# Percep_o_Externa.net
KiCad netlist of a schematic drawn in Altium Designer
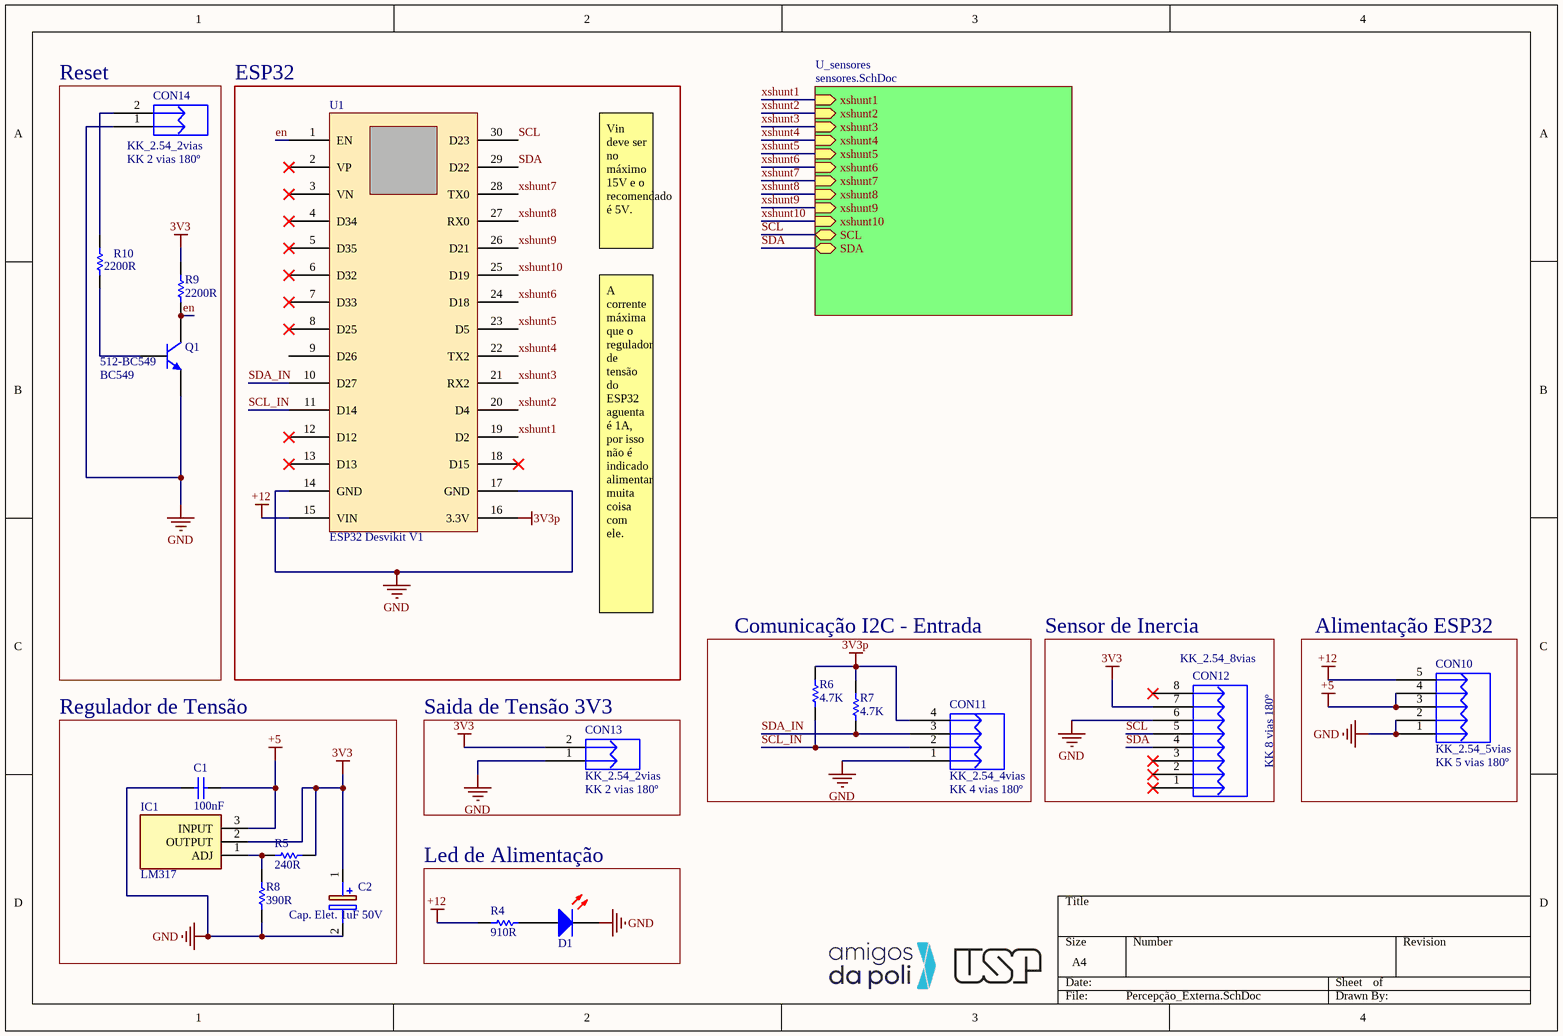
[diagram p0: Percepção_Externa.SchDoc]

(export (version "E")
  (design (tool "Eeschema 10.0.6"))
  (components
    (comp (ref "C1")
      (value "100nF")
      (footprint "CAP CER DISK 100NF 50V")
      (description "CAP CER DISK 100NF 50V")
      (fields (field (name "MANUFACTURER PART NUMBER") "IMP14925"))
      (libsource (lib "Capacitores_SCHLIB") (part "CAP CER DISK 100NF 50V"))
    )
    (comp (ref "C2")
      (value "Cap. Elet. 1uF 50V")
      (footprint "Cap. Elet. 470uF 16V")
      (description "Aluminum Organic Polymer Capacitors 16volts 470uF ESR 10mohm")
      (fields
        (field (name "MANUFACTURER_PART_NUMBER") "16SEPC470M")
        (field (name "MOUSER PART NUMBER") "667-16SEPC470M")
      )
      (libsource (lib "esp32") (part "Cap. Elet. 470 uF 16V"))
    )
    (comp (ref "CON10")
      (value "KK_2.54_5vias")
      (footprint "KK_5vias_180°")
      (description "Conector KK 2.54mm 5 vias")
      (fields (field (name "VALOR") "KK 5 vias 180º"))
      (libsource (lib "Conectores_Sch") (part "KK_2.54_5vias"))
    )
    (comp (ref "CON11")
      (value "KK_2.54_4vias")
      (footprint "KK_4vias_180°")
      (description "Conector KK 2.54mm 4 vias")
      (fields (field (name "VALOR") "KK 4 vias 180º"))
      (libsource (lib "Conectores_Sch") (part "KK_2.54_4vias"))
    )
    (comp (ref "CON12")
      (value "KK_2.54_8vias")
      (footprint "KK_8vias_180°")
      (description "Conector KK 2.54mm 8 vias")
      (fields (field (name "VALOR") "KK 8 vias 180º"))
      (libsource (lib "Conectores_Sch") (part "KK_2.54_8vias"))
    )
    (comp (ref "CON13")
      (value "KK_2.54_2vias")
      (footprint "KK_2VIAS_180º")
      (description "Conector KK 2.54mm 2 vias")
      (fields (field (name "VALOR") "KK 2 vias 180º"))
      (libsource (lib "Conectores_Sch") (part "KK_2.54_2vias"))
    )
    (comp (ref "CON14")
      (value "KK_2.54_2vias")
      (footprint "KK_2VIAS_180º")
      (description "Conector KK 2.54mm 2 vias")
      (fields (field (name "VALOR") "KK 2 vias 180º"))
      (libsource (lib "Conectores_Sch") (part "KK_2.54_2vias"))
    )
    (comp (ref "D1")
      (value "LED 5MM RED")
      (footprint "LED 5MM RED")
      (fields (field (name "MANUFACTURER") "Paralight") (field (name "MANUFACTURER PART NUMBER") "IMP585"))
      (libsource (lib "esp32") (part "LED 5MM RED"))
    )
    (comp (ref "IC1")
      (value "LM317")
      (footprint "SamacSys:TO254P467X1016X1971-3P")
      (description "Integrated Circuit")
      (libsource (lib "*") (part "LM317"))
    )
    (comp (ref "Q1")
      (value "BC549")
      (footprint "TO92")
      (description "TRANS NPN 30V 0.1A TO-92")
      (fields
        (field (name "MANUFACTURER") "Fairchild Semiconductor")
        (field (name "SUPPLIER PART NUMBER 1") "512-BC549")
      )
      (libsource (lib "PS_Balanca") (part "BC549"))
    )
    (comp (ref "R4")
      (value "RES 470R 1/4W CARBON FILM")
      (footprint "RES 470R 1/4W CARBON FILM")
      (description "RES 470R OHM 1/4W 5% CARBON FILM")
      (fields
        (field (name "MANUFACTURER") "Ty-Ohm")
        (field (name "MANUFACTURER PART NUMBER") "CR25")
        (field (name "RESISTANCE (OHMS)") "910R")
      )
      (libsource (lib "esp32") (part "RES 470R 1/4W CARBON FILM"))
    )
    (comp (ref "R5")
      (value "RES 470R 1/4W CARBON FILM")
      (footprint "RES 470R 1/4W CARBON FILM")
      (description "RES 470R OHM 1/4W 5% CARBON FILM")
      (fields
        (field (name "MANUFACTURER") "Ty-Ohm")
        (field (name "MANUFACTURER PART NUMBER") "CR25")
        (field (name "RESISTANCE (OHMS)") "240R")
      )
      (libsource (lib "esp32") (part "RES 470R 1/4W CARBON FILM"))
    )
    (comp (ref "R6")
      (value "4.7K")
      (footprint "RES 4.7K 1/4W CARBON FILM")
      (description "RES 4.7K OHM 1/4W 5% CARBON FILM")
      (fields (field (name "MANUFACTURER") "Ty-Ohm") (field (name "MANUFACTURER PART NUMBER") "CR25"))
      (libsource (lib "esp32") (part "RES 4.7K 1/4W CARBON FILM"))
    )
    (comp (ref "R7")
      (value "4.7K")
      (footprint "RES 4.7K 1/4W CARBON FILM")
      (description "RES 4.7K OHM 1/4W 5% CARBON FILM")
      (fields (field (name "MANUFACTURER") "Ty-Ohm") (field (name "MANUFACTURER PART NUMBER") "CR25"))
      (libsource (lib "esp32") (part "RES 4.7K 1/4W CARBON FILM"))
    )
    (comp (ref "R8")
      (value "RES 470R 1/4W CARBON FILM")
      (footprint "RES 470R 1/4W CARBON FILM")
      (description "RES 470R OHM 1/4W 5% CARBON FILM")
      (fields
        (field (name "MANUFACTURER") "Ty-Ohm")
        (field (name "MANUFACTURER PART NUMBER") "CR25")
        (field (name "RESISTANCE (OHMS)") "390R")
      )
      (libsource (lib "esp32") (part "RES 470R 1/4W CARBON FILM"))
    )
    (comp (ref "R9")
      (value "RES 470R 1/4W CARBON FILM")
      (footprint "RES 470R 1/4W CARBON FILM")
      (description "RES 470R OHM 1/4W 5% CARBON FILM")
      (fields
        (field (name "MANUFACTURER") "Ty-Ohm")
        (field (name "MANUFACTURER PART NUMBER") "CR25")
        (field (name "RESISTANCE (OHMS)") "2200R")
      )
      (libsource (lib "esp32") (part "RES 470R 1/4W CARBON FILM"))
    )
    (comp (ref "R10")
      (value "RES 470R 1/4W CARBON FILM")
      (footprint "RES 470R 1/4W CARBON FILM")
      (description "RES 470R OHM 1/4W 5% CARBON FILM")
      (fields
        (field (name "MANUFACTURER") "Ty-Ohm")
        (field (name "MANUFACTURER PART NUMBER") "CR25")
        (field (name "RESISTANCE (OHMS)") "2200R")
      )
      (libsource (lib "esp32") (part "RES 470R 1/4W CARBON FILM"))
    )
    (comp (ref "U1")
      (value "ESP32 Desvikit V1")
      (footprint "ESP32_Desvikit_v1")
      (description "microcontrolador com moculo bluethoth e wifi")
      (fields (field (name "Comment") "microcontrolador"))
      (libsource (lib "esp32") (part "ESP32 Desvikit v1"))
    )
  )
  (nets
    (net (code "1") (name "+5") (class "Default")
      (node (ref "C1") (pin "2") (pinfunction "2_2") (pintype "passive"))
      (node (ref "CON10") (pin "3") (pintype "passive"))
      (node (ref "CON10") (pin "4") (pintype "passive"))
      (node (ref "IC1") (pin "3") (pinfunction "INPUT_3") (pintype "passive"))
    )
    (net (code "2") (name "+12") (class "Default")
      (node (ref "CON10") (pin "5") (pintype "passive"))
      (node (ref "R4") (pin "2") (pinfunction "2_2") (pintype "passive"))
      (node (ref "U1") (pin "15") (pinfunction "VIN_15") (pintype "passive"))
    )
    (net (code "3") (name "/SCL") (class "Default")
      (node (ref "CON12") (pin "5") (pintype "passive"))
      (node (ref "U1") (pin "30") (pinfunction "D23_30") (pintype "passive"))
    )
    (net (code "4") (name "/SCL_IN") (class "Default")
      (node (ref "CON11") (pin "2") (pintype "passive"))
      (node (ref "R6") (pin "2") (pinfunction "2_2") (pintype "passive"))
      (node (ref "U1") (pin "11") (pinfunction "D14_11") (pintype "passive"))
    )
    (net (code "5") (name "/SDA") (class "Default")
      (node (ref "CON12") (pin "4") (pintype "passive"))
      (node (ref "U1") (pin "29") (pinfunction "D22_29") (pintype "passive"))
    )
    (net (code "6") (name "/SDA_IN") (class "Default")
      (node (ref "CON11") (pin "3") (pintype "passive"))
      (node (ref "R7") (pin "2") (pinfunction "2_2") (pintype "passive"))
      (node (ref "U1") (pin "10") (pinfunction "D27_10") (pintype "passive"))
    )
    (net (code "7") (name "/en") (class "Default")
      (node (ref "Q1") (pin "1") (pinfunction "C_1") (pintype "passive"))
      (node (ref "R9") (pin "1") (pinfunction "1_1") (pintype "passive"))
      (node (ref "U1") (pin "1") (pinfunction "EN_1") (pintype "passive"))
    )
    (net (code "8") (name "/xshunt1") (class "Default")
      (node (ref "U1") (pin "19") (pinfunction "D2_19") (pintype "passive"))
    )
    (net (code "9") (name "/xshunt2") (class "Default")
      (node (ref "U1") (pin "20") (pinfunction "D4_20") (pintype "passive"))
    )
    (net (code "10") (name "/xshunt3") (class "Default")
      (node (ref "U1") (pin "21") (pinfunction "RX2_21") (pintype "passive"))
    )
    (net (code "11") (name "/xshunt4") (class "Default")
      (node (ref "U1") (pin "22") (pinfunction "TX2_22") (pintype "passive"))
    )
    (net (code "12") (name "/xshunt5") (class "Default")
      (node (ref "U1") (pin "23") (pinfunction "D5_23") (pintype "passive"))
    )
    (net (code "13") (name "/xshunt6") (class "Default")
      (node (ref "U1") (pin "24") (pinfunction "D18_24") (pintype "passive"))
    )
    (net (code "14") (name "/xshunt7") (class "Default")
      (node (ref "U1") (pin "28") (pinfunction "TX0_28") (pintype "passive"))
    )
    (net (code "15") (name "/xshunt8") (class "Default")
      (node (ref "U1") (pin "27") (pinfunction "RX0_27") (pintype "passive"))
    )
    (net (code "16") (name "/xshunt9") (class "Default")
      (node (ref "U1") (pin "26") (pinfunction "D21_26") (pintype "passive"))
    )
    (net (code "17") (name "/xshunt10") (class "Default")
      (node (ref "U1") (pin "25") (pinfunction "D19_25") (pintype "passive"))
    )
    (net (code "18") (name "3V3") (class "Default")
      (node (ref "C2") (pin "1") (pinfunction "+_1") (pintype "passive"))
      (node (ref "CON12") (pin "7") (pintype "passive"))
      (node (ref "CON13") (pin "2") (pintype "passive"))
      (node (ref "IC1") (pin "2") (pinfunction "OUTPUT_2") (pintype "passive"))
      (node (ref "R5") (pin "2") (pinfunction "2_2") (pintype "passive"))
      (node (ref "R9") (pin "2") (pinfunction "2_2") (pintype "passive"))
    )
    (net (code "19") (name "3V3p") (class "Default")
      (node (ref "CON11") (pin "4") (pintype "passive"))
      (node (ref "R6") (pin "1") (pinfunction "1_1") (pintype "passive"))
      (node (ref "R7") (pin "1") (pinfunction "1_1") (pintype "passive"))
      (node (ref "U1") (pin "16") (pinfunction "3.3V_16") (pintype "passive"))
    )
    (net (code "20") (name "GND") (class "Default")
      (node (ref "C1") (pin "1") (pinfunction "1_1") (pintype "passive"))
      (node (ref "C2") (pin "2") (pinfunction "-_2") (pintype "passive"))
      (node (ref "CON10") (pin "1") (pintype "passive"))
      (node (ref "CON10") (pin "2") (pintype "passive"))
      (node (ref "CON11") (pin "1") (pintype "passive"))
      (node (ref "CON12") (pin "6") (pintype "passive"))
      (node (ref "CON13") (pin "1") (pintype "passive"))
      (node (ref "CON14") (pin "1") (pintype "passive"))
      (node (ref "D1") (pin "2") (pinfunction "K_2") (pintype "passive"))
      (node (ref "Q1") (pin "3") (pinfunction "E_3") (pintype "passive"))
      (node (ref "R8") (pin "1") (pinfunction "1_1") (pintype "passive"))
      (node (ref "U1") (pin "14") (pinfunction "GND_14") (pintype "passive"))
      (node (ref "U1") (pin "17") (pinfunction "GND_17") (pintype "passive"))
    )
    (net (code "21") (name "Net-(CON14-Pad2)") (class "Default")
      (node (ref "CON14") (pin "2") (pintype "passive"))
      (node (ref "R10") (pin "2") (pinfunction "2_2") (pintype "passive"))
    )
    (net (code "22") (name "Net-(D1-A)") (class "Default")
      (node (ref "D1") (pin "1") (pinfunction "A_1") (pintype "passive"))
      (node (ref "R4") (pin "1") (pinfunction "1_1") (pintype "passive"))
    )
    (net (code "23") (name "Net-(IC1-ADJ)") (class "Default")
      (node (ref "IC1") (pin "1") (pinfunction "ADJ_1") (pintype "passive"))
      (node (ref "R5") (pin "1") (pinfunction "1_1") (pintype "passive"))
      (node (ref "R8") (pin "2") (pinfunction "2_2") (pintype "passive"))
    )
    (net (code "24") (name "Net-(Q1-B)") (class "Default")
      (node (ref "Q1") (pin "2") (pinfunction "B_2") (pintype "passive"))
      (node (ref "R10") (pin "1") (pinfunction "1_1") (pintype "passive"))
    )
    (net (code "25") (name "unconnected-(CON12-Pad1)") (class "Default")
      (node (ref "CON12") (pin "1") (pintype "passive+no_connect"))
    )
    (net (code "26") (name "unconnected-(CON12-Pad2)") (class "Default")
      (node (ref "CON12") (pin "2") (pintype "passive+no_connect"))
    )
    (net (code "27") (name "unconnected-(CON12-Pad3)") (class "Default")
      (node (ref "CON12") (pin "3") (pintype "passive+no_connect"))
    )
    (net (code "28") (name "unconnected-(CON12-Pad8)") (class "Default")
      (node (ref "CON12") (pin "8") (pintype "passive+no_connect"))
    )
    (net (code "29") (name "unconnected-(U1-D12-Pad12)") (class "Default")
      (node (ref "U1") (pin "12") (pinfunction "D12_12") (pintype "passive+no_connect"))
    )
    (net (code "30") (name "unconnected-(U1-D13-Pad13)") (class "Default")
      (node (ref "U1") (pin "13") (pinfunction "D13_13") (pintype "passive+no_connect"))
    )
    (net (code "31") (name "unconnected-(U1-D15-Pad18)") (class "Default")
      (node (ref "U1") (pin "18") (pinfunction "D15_18") (pintype "passive+no_connect"))
    )
    (net (code "32") (name "unconnected-(U1-D25-Pad8)") (class "Default")
      (node (ref "U1") (pin "8") (pinfunction "D25_8") (pintype "passive+no_connect"))
    )
    (net (code "33") (name "unconnected-(U1-D26-Pad9)") (class "Default")
      (node (ref "U1") (pin "9") (pinfunction "D26_9") (pintype "passive"))
    )
    (net (code "34") (name "unconnected-(U1-D32-Pad6)") (class "Default")
      (node (ref "U1") (pin "6") (pinfunction "D32_6") (pintype "passive+no_connect"))
    )
    (net (code "35") (name "unconnected-(U1-D33-Pad7)") (class "Default")
      (node (ref "U1") (pin "7") (pinfunction "D33_7") (pintype "passive+no_connect"))
    )
    (net (code "36") (name "unconnected-(U1-D34-Pad4)") (class "Default")
      (node (ref "U1") (pin "4") (pinfunction "D34_4") (pintype "passive+no_connect"))
    )
    (net (code "37") (name "unconnected-(U1-D35-Pad5)") (class "Default")
      (node (ref "U1") (pin "5") (pinfunction "D35_5") (pintype "passive+no_connect"))
    )
    (net (code "38") (name "unconnected-(U1-VN-Pad3)") (class "Default")
      (node (ref "U1") (pin "3") (pinfunction "VN_3") (pintype "passive+no_connect"))
    )
    (net (code "39") (name "unconnected-(U1-VP-Pad2)") (class "Default")
      (node (ref "U1") (pin "2") (pinfunction "VP_2") (pintype "passive+no_connect"))
    )
  )
)
